# 780-00055_rev1_Pg5_SCH_NRES_Temp_Meas_8-.net
KiCad netlist of a schematic drawn in Altium Designer
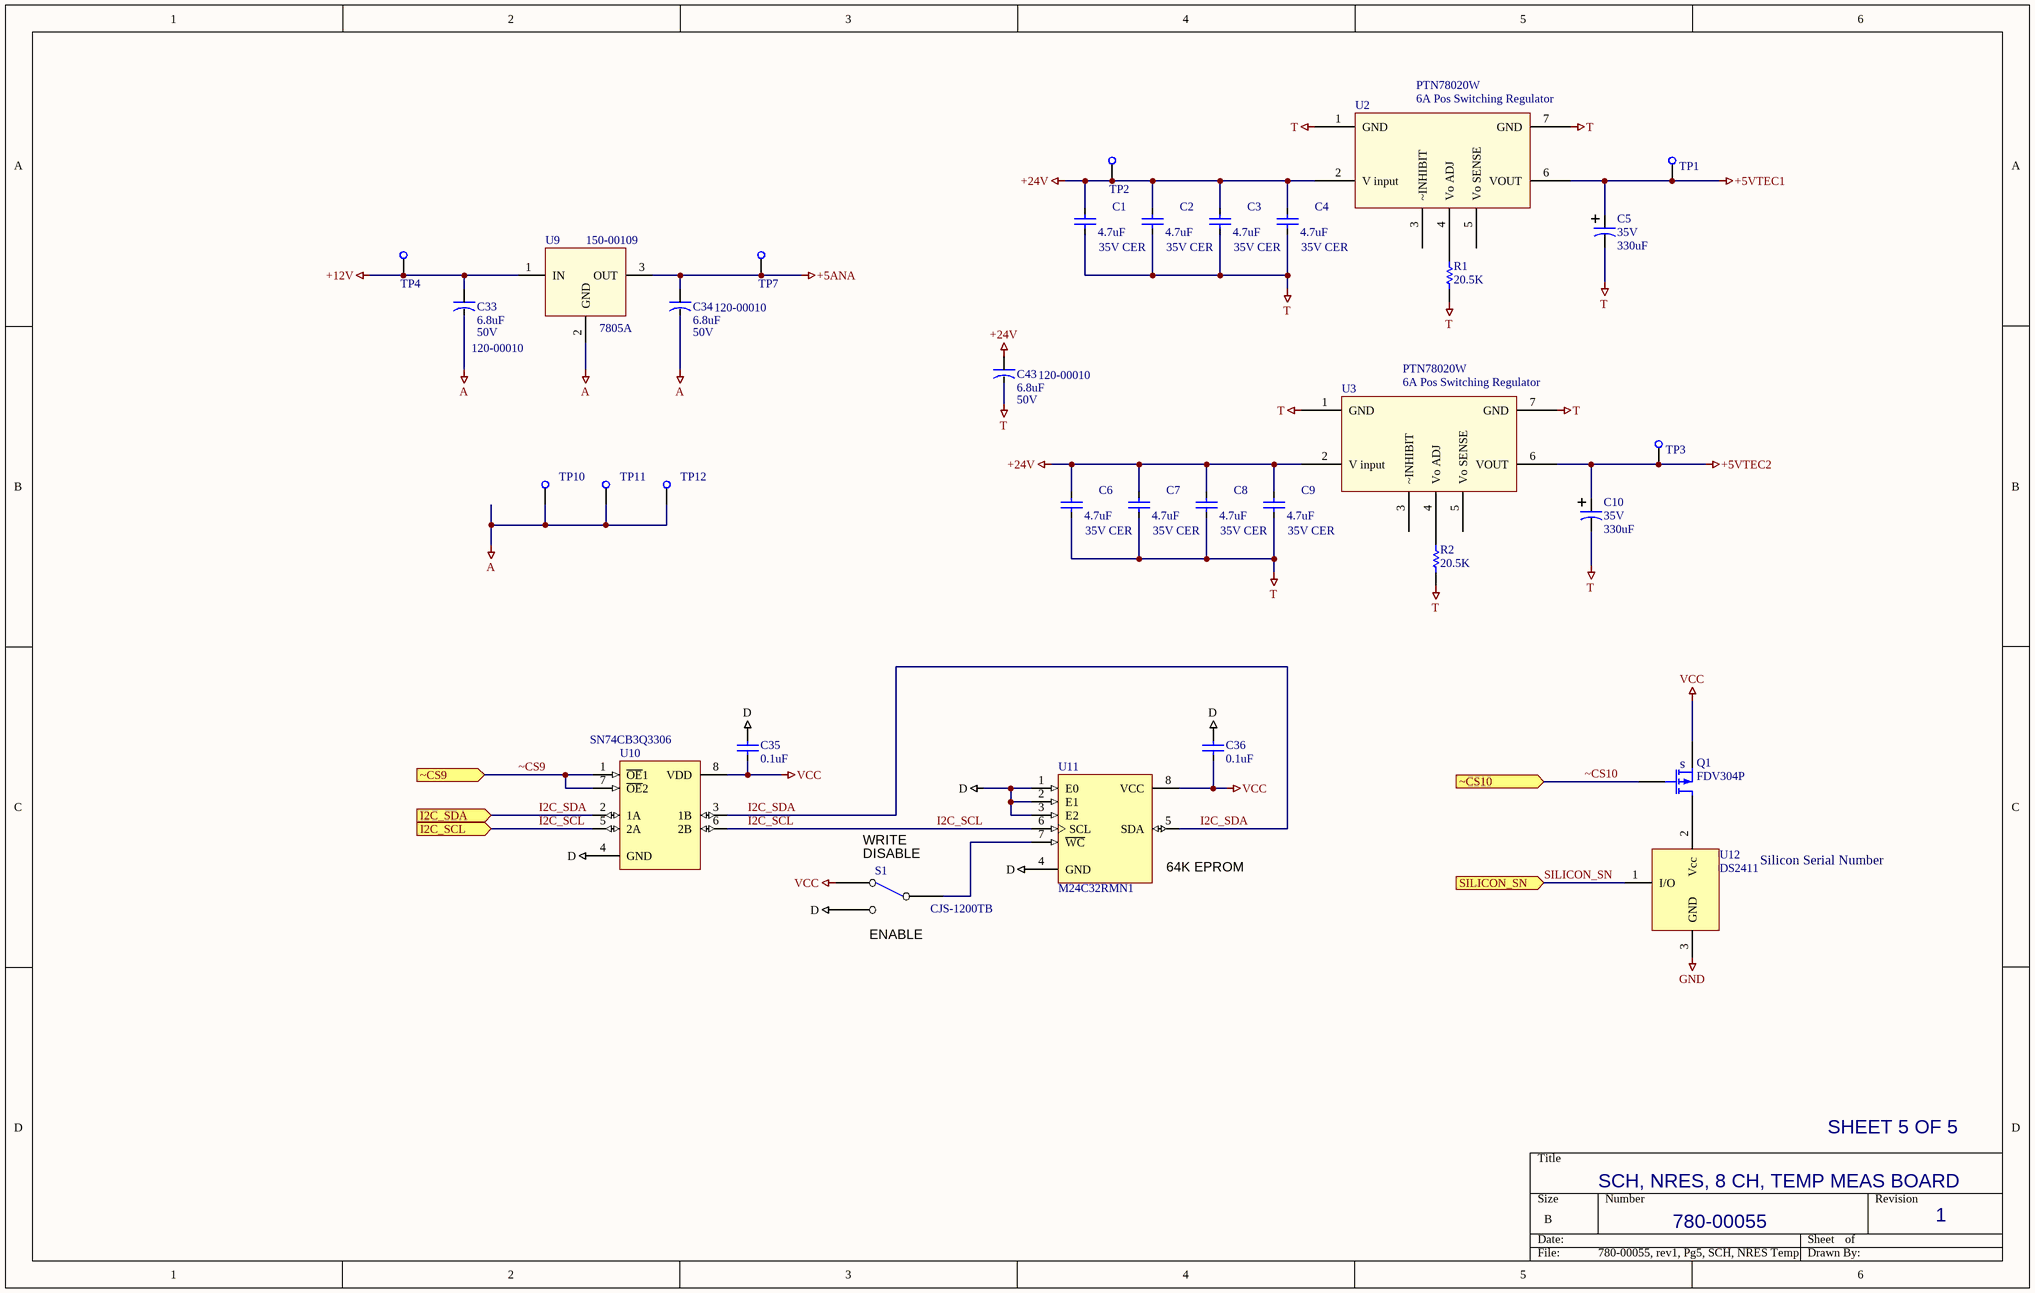
[diagram p0: 780-00055, rev1, Pg5, SCH, NRES Temp Meas, 8-Chan RTD .SchDoc]

(export (version "E")
  (design (tool "Eeschema 10.0.6"))
  (components
    (comp (ref "C1")
      (value "35V CER")
      (footprint "SMD_0805")
      (description "Capacitor")
      (fields (field (name "ALTIUM_VALUE") "4.7uF"))
      (libsource (lib "Richs Schematic Components") (part "Cap SMD"))
    )
    (comp (ref "C2")
      (value "35V CER")
      (footprint "SMD_0805")
      (description "Capacitor")
      (fields (field (name "ALTIUM_VALUE") "4.7uF"))
      (libsource (lib "Richs Schematic Components") (part "Cap SMD"))
    )
    (comp (ref "C3")
      (value "35V CER")
      (footprint "SMD_0805")
      (description "Capacitor")
      (fields (field (name "ALTIUM_VALUE") "4.7uF"))
      (libsource (lib "Richs Schematic Components") (part "Cap SMD"))
    )
    (comp (ref "C4")
      (value "35V CER")
      (footprint "SMD_0805")
      (description "Capacitor")
      (fields (field (name "ALTIUM_VALUE") "4.7uF"))
      (libsource (lib "Richs Schematic Components") (part "Cap SMD"))
    )
    (comp (ref "C5")
      (value "35V")
      (footprint "CAP, Thru Hole 10mm dia")
      (description "Radial Thru hole")
      (fields (field (name "ALTIUM_VALUE") "330uF"))
      (libsource (lib "Richs Schematic Components") (part "Cap Elec, 330 uF, 35V"))
    )
    (comp (ref "C6")
      (value "35V CER")
      (footprint "SMD_0805")
      (description "Capacitor")
      (fields (field (name "ALTIUM_VALUE") "4.7uF"))
      (libsource (lib "Richs Schematic Components") (part "Cap SMD"))
    )
    (comp (ref "C7")
      (value "35V CER")
      (footprint "SMD_0805")
      (description "Capacitor")
      (fields (field (name "ALTIUM_VALUE") "4.7uF"))
      (libsource (lib "Richs Schematic Components") (part "Cap SMD"))
    )
    (comp (ref "C8")
      (value "35V CER")
      (footprint "SMD_0805")
      (description "Capacitor")
      (fields (field (name "ALTIUM_VALUE") "4.7uF"))
      (libsource (lib "Richs Schematic Components") (part "Cap SMD"))
    )
    (comp (ref "C9")
      (value "35V CER")
      (footprint "SMD_0805")
      (description "Capacitor")
      (fields (field (name "ALTIUM_VALUE") "4.7uF"))
      (libsource (lib "Richs Schematic Components") (part "Cap SMD"))
    )
    (comp (ref "C10")
      (value "35V")
      (footprint "CAP, Thru Hole 10mm dia")
      (description "Radial Thru hole")
      (fields (field (name "ALTIUM_VALUE") "330uF"))
      (libsource (lib "Richs Schematic Components") (part "Cap Elec, 330 uF, 35V"))
    )
    (comp (ref "C33")
      (value "50V")
      (footprint "SMD_CAP_6032")
      (description "outline 6.0mm x 3.2mm")
      (fields
        (field (name "ALTIUM_VALUE") "6.8uF")
        (field (name "MANUFACTURER") "AVX")
        (field (name "LCO P/N") "120-00010")
      )
      (libsource (lib "Richs Schematic Components") (part "Cap Tant 35V"))
    )
    (comp (ref "C34")
      (value "50V")
      (footprint "SMD_CAP_6032")
      (description "outline 6.0mm x 3.2mm")
      (fields
        (field (name "ALTIUM_VALUE") "6.8uF")
        (field (name "MANUFACTURER") "AVX")
        (field (name "LCO P/N") "120-00010")
      )
      (libsource (lib "Richs Schematic Components") (part "Cap Tant 35V"))
    )
    (comp (ref "C35")
      (value "0.1uF")
      (footprint "SMD_0805")
      (description "Capacitor")
      (fields (field (name "MANUFACTURER") "AVX") (field (name "Comment") "Cap SMD"))
      (libsource (lib "Richs Schematic Components") (part "Cap SMD"))
    )
    (comp (ref "C36")
      (value "0.1uF")
      (footprint "SMD_0805")
      (description "Capacitor")
      (fields (field (name "MANUFACTURER") "AVX") (field (name "Comment") "Cap SMD"))
      (libsource (lib "Richs Schematic Components") (part "Cap SMD"))
    )
    (comp (ref "C43")
      (value "50V")
      (footprint "SMD_CAP_6032")
      (description "outline 6.0mm x 3.2mm")
      (fields
        (field (name "ALTIUM_VALUE") "6.8uF")
        (field (name "MANUFACTURER") "AVX")
        (field (name "LCO P/N") "120-00010")
      )
      (libsource (lib "Richs Schematic Components") (part "Cap Tant 35V"))
    )
    (comp (ref "Q1")
      (value "FDV304P")
      (footprint "SMD_SOT23_3")
      (description "P-MOSFET LOGIC LEVEL")
      (fields (field (name "MANUFACTURER") "Fairchild"))
      (libsource (lib "Richs Schematic Components") (part "FDV304P"))
    )
    (comp (ref "R1")
      (value "20.5K")
      (footprint "SMD_0805")
      (description "Resistor 0805")
      (fields (field (name "MANUFACTURER") "Vishay/Dale") (field (name "Comment") "Res 0805"))
      (libsource (lib "Richs Schematic Components") (part "Res SMD"))
    )
    (comp (ref "R2")
      (value "20.5K")
      (footprint "SMD_0805")
      (description "Resistor 0805")
      (fields (field (name "MANUFACTURER") "Vishay/Dale") (field (name "Comment") "Res 0805"))
      (libsource (lib "Richs Schematic Components") (part "Res SMD"))
    )
    (comp (ref "S1")
      (value "CJS-1200TB")
      (footprint "CAS-120B")
      (fields (field (name "MANUFACTURER") "Copal Electronics"))
      (libsource (lib "JON_1_Library") (part "SW_SPDT_DOUG"))
    )
    (comp (ref "TP1")
      (value "Test point")
      (footprint "Protel 99SE BANKS PCB:PAD_80D_052H")
      (description "Test Point")
      (fields (field (name "MANUFACTURER") "Keystone"))
      (libsource (lib "Richs Schematic Components") (part "Test point"))
    )
    (comp (ref "TP2")
      (value "Test point")
      (footprint "Protel 99SE BANKS PCB:PAD_80D_052H")
      (description "Test Point")
      (fields (field (name "MANUFACTURER") "Keystone"))
      (libsource (lib "Richs Schematic Components") (part "Test point"))
    )
    (comp (ref "TP3")
      (value "Test point")
      (footprint "Protel 99SE BANKS PCB:PAD_80D_052H")
      (description "Test Point")
      (fields (field (name "MANUFACTURER") "Keystone"))
      (libsource (lib "Richs Schematic Components") (part "Test point"))
    )
    (comp (ref "TP4")
      (value "Test point")
      (footprint "Protel 99SE BANKS PCB:PAD_80D_052H")
      (description "Test Point")
      (fields (field (name "MANUFACTURER") "Keystone"))
      (libsource (lib "Richs Schematic Components") (part "Test point"))
    )
    (comp (ref "TP7")
      (value "Test point")
      (footprint "Protel 99SE BANKS PCB:PAD_80D_052H")
      (description "Test Point")
      (fields (field (name "MANUFACTURER") "Keystone"))
      (libsource (lib "Richs Schematic Components") (part "Test point"))
    )
    (comp (ref "TP10")
      (value "Test point")
      (footprint "Protel 99SE BANKS PCB:PAD_80D_052H")
      (description "Test Point")
      (fields (field (name "MANUFACTURER") "Keystone"))
      (libsource (lib "Richs Schematic Components") (part "Test point"))
    )
    (comp (ref "TP11")
      (value "Test point")
      (footprint "Protel 99SE BANKS PCB:PAD_80D_052H")
      (description "Test Point")
      (fields (field (name "MANUFACTURER") "Keystone"))
      (libsource (lib "Richs Schematic Components") (part "Test point"))
    )
    (comp (ref "TP12")
      (value "Test point")
      (footprint "Protel 99SE BANKS PCB:PAD_80D_052H")
      (description "Test Point")
      (fields (field (name "MANUFACTURER") "Keystone"))
      (libsource (lib "Richs Schematic Components") (part "Test point"))
    )
    (comp (ref "U2")
      (value "6A Pos Switching Regulator")
      (footprint "TEXAS Inst Switching Regulator")
      (description "Pos Adj Switching Regulator")
      (fields (field (name "ALTIUM_VALUE") "PTN78020W"))
      (libsource (lib "Richs Schematic Components") (part "PTN78020W"))
    )
    (comp (ref "U3")
      (value "6A Pos Switching Regulator")
      (footprint "TEXAS Inst Switching Regulator")
      (description "Pos Adj Switching Regulator")
      (fields (field (name "ALTIUM_VALUE") "PTN78020W"))
      (libsource (lib "Richs Schematic Components") (part "PTN78020W"))
    )
    (comp (ref "U9")
      (value "7805A")
      (footprint "TO-220 w/Heatsink 7136DG")
      (fields
        (field (name "LCO P/N") "150-00109")
        (field (name "MANUFACTURER") "On Semi")
        (field (name "Comment") "Voltage Reg, Pos Fixed")
      )
      (libsource (lib "Richs Schematic Components") (part "Voltage Reg, Pos Fixed"))
    )
    (comp (ref "U10")
      (value "SN74CB3Q3306")
      (footprint "PW008_N")
      (description "Dual FET Bus Switch")
      (fields (field (name "MANUFACTURER") "TI") (field (name "Comment") "SN74CBT3306PWLE"))
      (libsource (lib "TI Logic Switch") (part "SN74CBT3306PWLE"))
    )
    (comp (ref "U11")
      (value "M24C32RMN1")
      (footprint "SOP8_N")
      (description "32 Kbit Serial I²C Bus EEPROM")
      (libsource (lib "ST Memory EEPROM Serial") (part "M24C32RMN1"))
    )
    (comp (ref "U12")
      (value "DS2411")
      (footprint "SMD_SOT23_3")
      (description "Silicon Serial Number")
      (fields (field (name "MANUFACTURER") "MAXIM"))
      (libsource (lib "Richs Schematic Components") (part "DS2411"))
    )
  )
  (nets
    (net (code "1") (name "+5ANA") (class "Default")
      (node (ref "C34") (pin "pos") (pinfunction "1_pos") (pintype "passive"))
      (node (ref "TP7") (pin "1") (pinfunction "TP_1") (pintype "passive"))
      (node (ref "U9") (pin "3") (pinfunction "OUT_3") (pintype "passive"))
    )
    (net (code "2") (name "+5VTEC1") (class "Default")
      (node (ref "C5") (pin "1") (pinfunction "1_1") (pintype "passive"))
      (node (ref "TP1") (pin "1") (pinfunction "TP_1") (pintype "passive"))
      (node (ref "U2") (pin "6") (pinfunction "VOUT_6") (pintype "passive"))
    )
    (net (code "3") (name "+5VTEC2") (class "Default")
      (node (ref "C10") (pin "1") (pinfunction "1_1") (pintype "passive"))
      (node (ref "TP3") (pin "1") (pinfunction "TP_1") (pintype "passive"))
      (node (ref "U3") (pin "6") (pinfunction "VOUT_6") (pintype "passive"))
    )
    (net (code "4") (name "+12V") (class "Default")
      (node (ref "C33") (pin "pos") (pinfunction "1_pos") (pintype "passive"))
      (node (ref "TP4") (pin "1") (pinfunction "TP_1") (pintype "passive"))
      (node (ref "U9") (pin "1") (pinfunction "IN_1") (pintype "passive"))
    )
    (net (code "5") (name "+24V") (class "Default")
      (node (ref "C1") (pin "2") (pinfunction "2_2") (pintype "passive"))
      (node (ref "C2") (pin "2") (pinfunction "2_2") (pintype "passive"))
      (node (ref "C3") (pin "2") (pinfunction "2_2") (pintype "passive"))
      (node (ref "C4") (pin "2") (pinfunction "2_2") (pintype "passive"))
      (node (ref "C43") (pin "pos") (pinfunction "1_pos") (pintype "passive"))
      (node (ref "C6") (pin "2") (pinfunction "2_2") (pintype "passive"))
      (node (ref "C7") (pin "2") (pinfunction "2_2") (pintype "passive"))
      (node (ref "C8") (pin "2") (pinfunction "2_2") (pintype "passive"))
      (node (ref "C9") (pin "2") (pinfunction "2_2") (pintype "passive"))
      (node (ref "TP2") (pin "1") (pinfunction "TP_1") (pintype "passive"))
      (node (ref "U2") (pin "2") (pinfunction "V_input_2") (pintype "passive"))
      (node (ref "U3") (pin "2") (pinfunction "V_input_2") (pintype "passive"))
    )
    (net (code "6") (name "/I2C_SCL") (class "Default")
      (node (ref "U10") (pin "5") (pinfunction "2A_5") (pintype "bidirectional"))
      (node (ref "U10") (pin "6") (pinfunction "2B_6") (pintype "bidirectional"))
      (node (ref "U11") (pin "6") (pinfunction "SCL_6") (pintype "input"))
    )
    (net (code "7") (name "/I2C_SDA") (class "Default")
      (node (ref "U10") (pin "2") (pinfunction "1A_2") (pintype "bidirectional"))
      (node (ref "U10") (pin "3") (pinfunction "1B_3") (pintype "bidirectional"))
      (node (ref "U11") (pin "5") (pinfunction "SDA_5") (pintype "bidirectional"))
    )
    (net (code "8") (name "/SILICON_SN") (class "Default")
      (node (ref "U12") (pin "1") (pinfunction "I/O_1") (pintype "passive"))
    )
    (net (code "9") (name "/~CS9") (class "Default")
      (node (ref "U10") (pin "1") (pinfunction "~{OE}1_1") (pintype "input"))
      (node (ref "U10") (pin "7") (pinfunction "~{OE}2_7") (pintype "input"))
    )
    (net (code "10") (name "/~CS10") (class "Default")
      (node (ref "Q1") (pin "1") (pinfunction "G_1") (pintype "passive"))
    )
    (net (code "11") (name "A") (class "Default")
      (node (ref "C33") (pin "neg") (pinfunction "2_neg") (pintype "passive"))
      (node (ref "C34") (pin "neg") (pinfunction "2_neg") (pintype "passive"))
      (node (ref "TP10") (pin "1") (pinfunction "TP_1") (pintype "passive"))
      (node (ref "TP11") (pin "1") (pinfunction "TP_1") (pintype "passive"))
      (node (ref "TP12") (pin "1") (pinfunction "TP_1") (pintype "passive"))
      (node (ref "U9") (pin "2") (pinfunction "GND_2") (pintype "passive"))
    )
    (net (code "12") (name "D") (class "Default")
      (node (ref "C35") (pin "2") (pinfunction "2_2") (pintype "passive"))
      (node (ref "C36") (pin "2") (pinfunction "2_2") (pintype "passive"))
      (node (ref "S1") (pin "1") (pinfunction "NO_1") (pintype "passive"))
      (node (ref "U10") (pin "4") (pinfunction "GND_4") (pintype "power_in"))
      (node (ref "U11") (pin "1") (pinfunction "E0_1") (pintype "input"))
      (node (ref "U11") (pin "2") (pinfunction "E1_2") (pintype "input"))
      (node (ref "U11") (pin "3") (pinfunction "E2_3") (pintype "input"))
      (node (ref "U11") (pin "4") (pinfunction "GND_4") (pintype "power_in"))
    )
    (net (code "13") (name "GND") (class "Default")
      (node (ref "U12") (pin "3") (pinfunction "GND_3") (pintype "passive"))
    )
    (net (code "14") (name "Net-(Q1-D)") (class "Default")
      (node (ref "Q1") (pin "3") (pinfunction "D_3") (pintype "passive"))
      (node (ref "U12") (pin "2") (pinfunction "Vcc_2") (pintype "passive"))
    )
    (net (code "15") (name "Net-(S1-COM)") (class "Default")
      (node (ref "S1") (pin "2") (pinfunction "COM_2") (pintype "passive"))
      (node (ref "U11") (pin "7") (pinfunction "~{WC}_7") (pintype "input"))
    )
    (net (code "16") (name "Net-(U2-Vo_ADJ)") (class "Default")
      (node (ref "R1") (pin "2") (pinfunction "2_2") (pintype "passive"))
      (node (ref "U2") (pin "4") (pinfunction "Vo_ADJ_4") (pintype "passive"))
    )
    (net (code "17") (name "Net-(U3-Vo_ADJ)") (class "Default")
      (node (ref "R2") (pin "2") (pinfunction "2_2") (pintype "passive"))
      (node (ref "U3") (pin "4") (pinfunction "Vo_ADJ_4") (pintype "passive"))
    )
    (net (code "18") (name "T") (class "Default")
      (node (ref "C1") (pin "1") (pinfunction "1_1") (pintype "passive"))
      (node (ref "C10") (pin "2") (pinfunction "2_2") (pintype "passive"))
      (node (ref "C2") (pin "1") (pinfunction "1_1") (pintype "passive"))
      (node (ref "C3") (pin "1") (pinfunction "1_1") (pintype "passive"))
      (node (ref "C4") (pin "1") (pinfunction "1_1") (pintype "passive"))
      (node (ref "C43") (pin "neg") (pinfunction "2_neg") (pintype "passive"))
      (node (ref "C5") (pin "2") (pinfunction "2_2") (pintype "passive"))
      (node (ref "C6") (pin "1") (pinfunction "1_1") (pintype "passive"))
      (node (ref "C7") (pin "1") (pinfunction "1_1") (pintype "passive"))
      (node (ref "C8") (pin "1") (pinfunction "1_1") (pintype "passive"))
      (node (ref "C9") (pin "1") (pinfunction "1_1") (pintype "passive"))
      (node (ref "R1") (pin "1") (pinfunction "1_1") (pintype "passive"))
      (node (ref "R2") (pin "1") (pinfunction "1_1") (pintype "passive"))
      (node (ref "U2") (pin "1") (pinfunction "GND_1") (pintype "passive"))
      (node (ref "U2") (pin "7") (pinfunction "GND_7") (pintype "passive"))
      (node (ref "U3") (pin "1") (pinfunction "GND_1") (pintype "passive"))
      (node (ref "U3") (pin "7") (pinfunction "GND_7") (pintype "passive"))
    )
    (net (code "19") (name "VCC") (class "Default")
      (node (ref "C35") (pin "1") (pinfunction "1_1") (pintype "passive"))
      (node (ref "C36") (pin "1") (pinfunction "1_1") (pintype "passive"))
      (node (ref "Q1") (pin "2") (pinfunction "S_2") (pintype "passive"))
      (node (ref "S1") (pin "3") (pinfunction "NC_3") (pintype "passive"))
      (node (ref "U10") (pin "8") (pinfunction "VDD_8") (pintype "power_in"))
      (node (ref "U11") (pin "8") (pinfunction "VCC_8") (pintype "power_in"))
    )
    (net (code "20") (name "unconnected-(U2-Vo_SENSE-Pad5)") (class "Default")
      (node (ref "U2") (pin "5") (pinfunction "Vo_SENSE_5") (pintype "passive"))
    )
    (net (code "21") (name "unconnected-(U2-~INHIBIT-Pad3)") (class "Default")
      (node (ref "U2") (pin "3") (pinfunction "~INHIBIT_3") (pintype "passive"))
    )
    (net (code "22") (name "unconnected-(U3-Vo_SENSE-Pad5)") (class "Default")
      (node (ref "U3") (pin "5") (pinfunction "Vo_SENSE_5") (pintype "passive"))
    )
    (net (code "23") (name "unconnected-(U3-~INHIBIT-Pad3)") (class "Default")
      (node (ref "U3") (pin "3") (pinfunction "~INHIBIT_3") (pintype "passive"))
    )
  )
)
